# memory.net
KiCad netlist of a schematic drawn in EAGLE
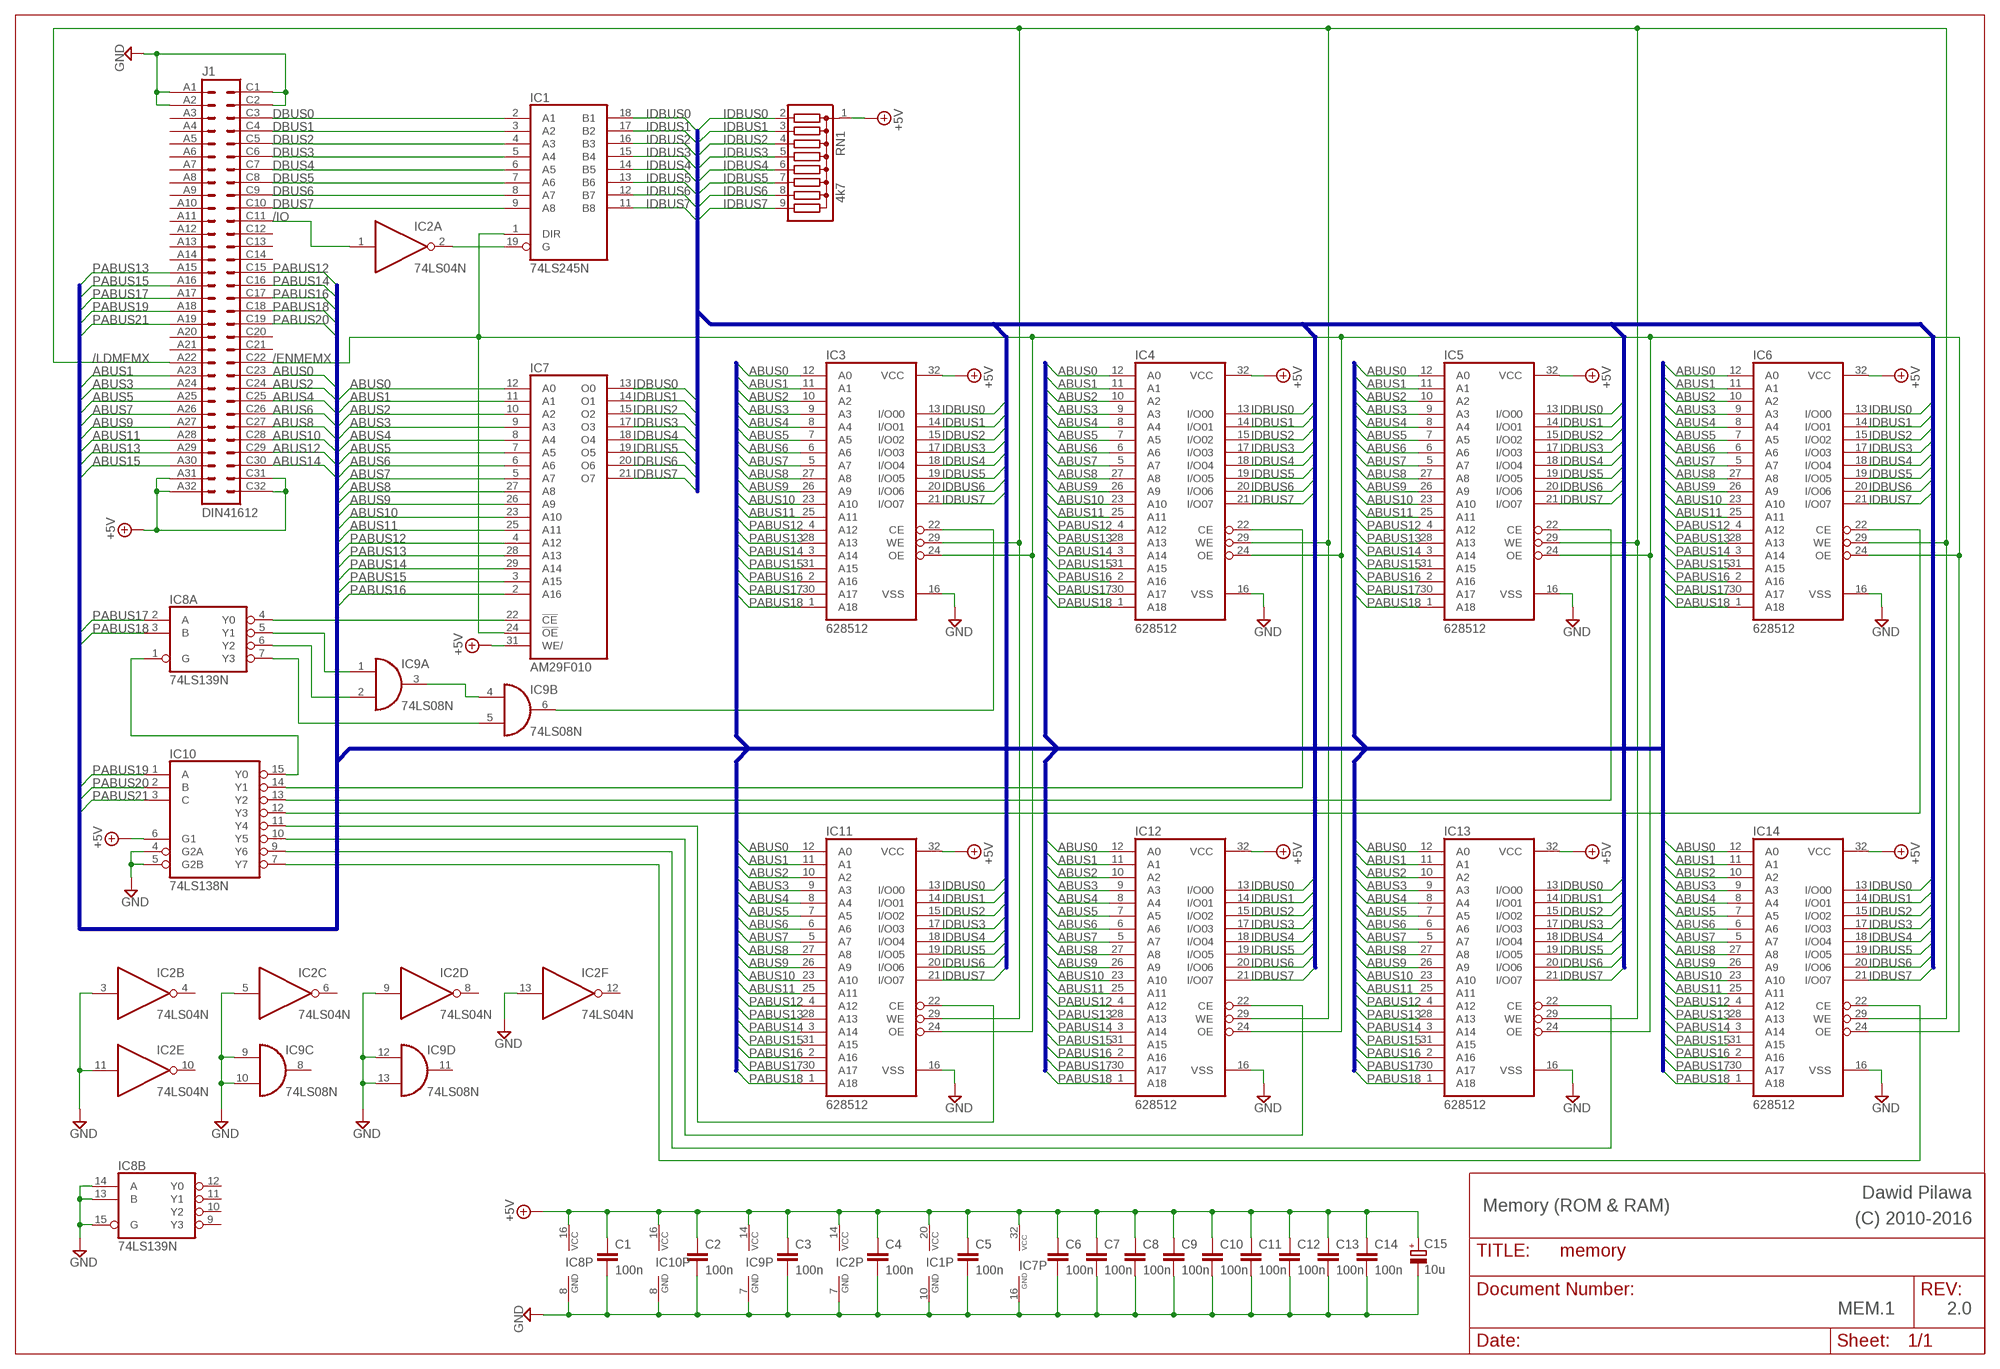
[diagram p0: schematic, sheet 1]

(export (version "E")
  (design (tool "Eeschema 10.0.6"))
  (components
    (comp (ref "C1")
      (value "100n")
      (footprint "eagle-import:C050-024X044")
      (libsource (lib "eagle-import") (part "C-EU050-024X044"))
    )
    (comp (ref "C2")
      (value "100n")
      (footprint "eagle-import:C050-024X044")
      (libsource (lib "eagle-import") (part "C-EU050-024X044"))
    )
    (comp (ref "C3")
      (value "100n")
      (footprint "eagle-import:C050-024X044")
      (libsource (lib "eagle-import") (part "C-EU050-024X044"))
    )
    (comp (ref "C4")
      (value "100n")
      (footprint "eagle-import:C050-024X044")
      (libsource (lib "eagle-import") (part "C-EU050-024X044"))
    )
    (comp (ref "C5")
      (value "100n")
      (footprint "eagle-import:C050-024X044")
      (libsource (lib "eagle-import") (part "C-EU050-024X044"))
    )
    (comp (ref "C6")
      (value "100n")
      (footprint "eagle-import:C050-024X044")
      (libsource (lib "eagle-import") (part "C-EU050-024X044"))
    )
    (comp (ref "C7")
      (value "100n")
      (footprint "eagle-import:C050-024X044")
      (libsource (lib "eagle-import") (part "C-EU050-024X044"))
    )
    (comp (ref "C8")
      (value "100n")
      (footprint "eagle-import:C050-024X044")
      (libsource (lib "eagle-import") (part "C-EU050-024X044"))
    )
    (comp (ref "C9")
      (value "100n")
      (footprint "eagle-import:C050-024X044")
      (libsource (lib "eagle-import") (part "C-EU050-024X044"))
    )
    (comp (ref "C10")
      (value "100n")
      (footprint "eagle-import:C050-024X044")
      (libsource (lib "eagle-import") (part "C-EU050-024X044"))
    )
    (comp (ref "C11")
      (value "100n")
      (footprint "eagle-import:C050-024X044")
      (libsource (lib "eagle-import") (part "C-EU050-024X044"))
    )
    (comp (ref "C12")
      (value "100n")
      (footprint "eagle-import:C050-024X044")
      (libsource (lib "eagle-import") (part "C-EU050-024X044"))
    )
    (comp (ref "C13")
      (value "100n")
      (footprint "eagle-import:C050-024X044")
      (libsource (lib "eagle-import") (part "C-EU050-024X044"))
    )
    (comp (ref "C14")
      (value "100n")
      (footprint "eagle-import:C050-024X044")
      (libsource (lib "eagle-import") (part "C-EU050-024X044"))
    )
    (comp (ref "C15")
      (value "10u")
      (footprint "eagle-import:E2,5-6")
      (libsource (lib "eagle-import") (part "CPOL-EUE2.5-6"))
    )
    (comp (ref "IC1")
      (value "74LS245N")
      (footprint "eagle-import:DIL20")
      (libsource (lib "eagle-import") (part "74245NLS"))
    )
    (comp (ref "IC2")
      (value "74LS04N")
      (footprint "eagle-import:DIL14")
      (libsource (lib "eagle-import") (part "7404NLS"))
    )
    (comp (ref "IC3")
      (value "628512")
      (footprint "eagle-import:DIL32")
      (libsource (lib "eagle-import") (part "HM628512A_DIL32"))
    )
    (comp (ref "IC4")
      (value "628512")
      (footprint "eagle-import:DIL32")
      (libsource (lib "eagle-import") (part "HM628512A_DIL32"))
    )
    (comp (ref "IC5")
      (value "628512")
      (footprint "eagle-import:DIL32")
      (libsource (lib "eagle-import") (part "HM628512A_DIL32"))
    )
    (comp (ref "IC6")
      (value "628512")
      (footprint "eagle-import:DIL32")
      (libsource (lib "eagle-import") (part "HM628512A_DIL32"))
    )
    (comp (ref "IC7")
      (value "AM29F010")
      (footprint "eagle-import:DIL32-6")
      (libsource (lib "eagle-import") (part "AM29F010"))
    )
    (comp (ref "IC8")
      (value "74LS139N")
      (footprint "eagle-import:DIL16")
      (libsource (lib "eagle-import") (part "74139NLS"))
    )
    (comp (ref "IC9")
      (value "74LS08N")
      (footprint "eagle-import:DIL14")
      (libsource (lib "eagle-import") (part "7408NLS"))
    )
    (comp (ref "IC10")
      (value "74LS138N")
      (footprint "eagle-import:DIL16")
      (libsource (lib "eagle-import") (part "74138NLS"))
    )
    (comp (ref "IC11")
      (value "628512")
      (footprint "eagle-import:DIL32")
      (libsource (lib "eagle-import") (part "HM628512A_DIL32"))
    )
    (comp (ref "IC12")
      (value "628512")
      (footprint "eagle-import:DIL32")
      (libsource (lib "eagle-import") (part "HM628512A_DIL32"))
    )
    (comp (ref "IC13")
      (value "628512")
      (footprint "eagle-import:DIL32")
      (libsource (lib "eagle-import") (part "HM628512A_DIL32"))
    )
    (comp (ref "IC14")
      (value "628512")
      (footprint "eagle-import:DIL32")
      (libsource (lib "eagle-import") (part "HM628512A_DIL32"))
    )
    (comp (ref "J1")
      (value "DIN41612")
      (footprint "eagle-import:VG64B")
      (libsource (lib "eagle-import") (part "VG64B"))
    )
    (comp (ref "RN1")
      (value "4k7")
      (footprint "eagle-import:SIL9")
      (libsource (lib "eagle-import") (part "G08R"))
    )
  )
  (nets
    (net (code "1") (name "+5V") (class "Default")
      (node (ref "C1") (pin "1") (pinfunction "1_1") (pintype "passive"))
      (node (ref "C10") (pin "1") (pinfunction "1_1") (pintype "passive"))
      (node (ref "C11") (pin "1") (pinfunction "1_1") (pintype "passive"))
      (node (ref "C12") (pin "1") (pinfunction "1_1") (pintype "passive"))
      (node (ref "C13") (pin "1") (pinfunction "1_1") (pintype "passive"))
      (node (ref "C14") (pin "1") (pinfunction "1_1") (pintype "passive"))
      (node (ref "C15") (pin "+") (pinfunction "+_+") (pintype "passive"))
      (node (ref "C2") (pin "1") (pinfunction "1_1") (pintype "passive"))
      (node (ref "C3") (pin "1") (pinfunction "1_1") (pintype "passive"))
      (node (ref "C4") (pin "1") (pinfunction "1_1") (pintype "passive"))
      (node (ref "C5") (pin "1") (pinfunction "1_1") (pintype "passive"))
      (node (ref "C6") (pin "1") (pinfunction "1_1") (pintype "passive"))
      (node (ref "C7") (pin "1") (pinfunction "1_1") (pintype "passive"))
      (node (ref "C8") (pin "1") (pinfunction "1_1") (pintype "passive"))
      (node (ref "C9") (pin "1") (pinfunction "1_1") (pintype "passive"))
      (node (ref "IC1") (pin "20") (pinfunction "VCC_20") (pintype "power_in"))
      (node (ref "IC10") (pin "16") (pinfunction "VCC_16") (pintype "power_in"))
      (node (ref "IC10") (pin "6") (pinfunction "G1_6") (pintype "input"))
      (node (ref "IC11") (pin "32") (pinfunction "VCC_32") (pintype "power_in"))
      (node (ref "IC12") (pin "32") (pinfunction "VCC_32") (pintype "power_in"))
      (node (ref "IC13") (pin "32") (pinfunction "VCC_32") (pintype "power_in"))
      (node (ref "IC14") (pin "32") (pinfunction "VCC_32") (pintype "power_in"))
      (node (ref "IC2") (pin "14") (pinfunction "VCC_14") (pintype "power_in"))
      (node (ref "IC3") (pin "32") (pinfunction "VCC_32") (pintype "power_in"))
      (node (ref "IC4") (pin "32") (pinfunction "VCC_32") (pintype "power_in"))
      (node (ref "IC5") (pin "32") (pinfunction "VCC_32") (pintype "power_in"))
      (node (ref "IC6") (pin "32") (pinfunction "VCC_32") (pintype "power_in"))
      (node (ref "IC7") (pin "31") (pinfunction "WE/_31") (pintype "input"))
      (node (ref "IC7") (pin "32") (pinfunction "VCC_32") (pintype "power_in"))
      (node (ref "IC8") (pin "16") (pinfunction "VCC_16") (pintype "power_in"))
      (node (ref "IC9") (pin "14") (pinfunction "VCC_14") (pintype "power_in"))
      (node (ref "J1") (pin "A31") (pinfunction "A31_A31") (pintype "passive"))
      (node (ref "J1") (pin "A32") (pinfunction "A32_A32") (pintype "passive"))
      (node (ref "J1") (pin "C31") (pinfunction "C31_C31") (pintype "passive"))
      (node (ref "J1") (pin "C32") (pinfunction "C32_C32") (pintype "passive"))
      (node (ref "RN1") (pin "1") (pinfunction "1_1") (pintype "passive"))
    )
    (net (code "2") (name "/ABUS0") (class "Default")
      (node (ref "IC11") (pin "12") (pinfunction "A0_12") (pintype "input"))
      (node (ref "IC12") (pin "12") (pinfunction "A0_12") (pintype "input"))
      (node (ref "IC13") (pin "12") (pinfunction "A0_12") (pintype "input"))
      (node (ref "IC14") (pin "12") (pinfunction "A0_12") (pintype "input"))
      (node (ref "IC3") (pin "12") (pinfunction "A0_12") (pintype "input"))
      (node (ref "IC4") (pin "12") (pinfunction "A0_12") (pintype "input"))
      (node (ref "IC5") (pin "12") (pinfunction "A0_12") (pintype "input"))
      (node (ref "IC6") (pin "12") (pinfunction "A0_12") (pintype "input"))
      (node (ref "IC7") (pin "12") (pinfunction "A0_12") (pintype "input"))
      (node (ref "J1") (pin "C23") (pinfunction "C23_C23") (pintype "passive"))
    )
    (net (code "3") (name "/ABUS1") (class "Default")
      (node (ref "IC11") (pin "11") (pinfunction "A1_11") (pintype "input"))
      (node (ref "IC12") (pin "11") (pinfunction "A1_11") (pintype "input"))
      (node (ref "IC13") (pin "11") (pinfunction "A1_11") (pintype "input"))
      (node (ref "IC14") (pin "11") (pinfunction "A1_11") (pintype "input"))
      (node (ref "IC3") (pin "11") (pinfunction "A1_11") (pintype "input"))
      (node (ref "IC4") (pin "11") (pinfunction "A1_11") (pintype "input"))
      (node (ref "IC5") (pin "11") (pinfunction "A1_11") (pintype "input"))
      (node (ref "IC6") (pin "11") (pinfunction "A1_11") (pintype "input"))
      (node (ref "IC7") (pin "11") (pinfunction "A1_11") (pintype "input"))
      (node (ref "J1") (pin "A23") (pinfunction "A23_A23") (pintype "passive"))
    )
    (net (code "4") (name "/ABUS2") (class "Default")
      (node (ref "IC11") (pin "10") (pinfunction "A2_10") (pintype "input"))
      (node (ref "IC12") (pin "10") (pinfunction "A2_10") (pintype "input"))
      (node (ref "IC13") (pin "10") (pinfunction "A2_10") (pintype "input"))
      (node (ref "IC14") (pin "10") (pinfunction "A2_10") (pintype "input"))
      (node (ref "IC3") (pin "10") (pinfunction "A2_10") (pintype "input"))
      (node (ref "IC4") (pin "10") (pinfunction "A2_10") (pintype "input"))
      (node (ref "IC5") (pin "10") (pinfunction "A2_10") (pintype "input"))
      (node (ref "IC6") (pin "10") (pinfunction "A2_10") (pintype "input"))
      (node (ref "IC7") (pin "10") (pinfunction "A2_10") (pintype "input"))
      (node (ref "J1") (pin "C24") (pinfunction "C24_C24") (pintype "passive"))
    )
    (net (code "5") (name "/ABUS3") (class "Default")
      (node (ref "IC11") (pin "9") (pinfunction "A3_9") (pintype "input"))
      (node (ref "IC12") (pin "9") (pinfunction "A3_9") (pintype "input"))
      (node (ref "IC13") (pin "9") (pinfunction "A3_9") (pintype "input"))
      (node (ref "IC14") (pin "9") (pinfunction "A3_9") (pintype "input"))
      (node (ref "IC3") (pin "9") (pinfunction "A3_9") (pintype "input"))
      (node (ref "IC4") (pin "9") (pinfunction "A3_9") (pintype "input"))
      (node (ref "IC5") (pin "9") (pinfunction "A3_9") (pintype "input"))
      (node (ref "IC6") (pin "9") (pinfunction "A3_9") (pintype "input"))
      (node (ref "IC7") (pin "9") (pinfunction "A3_9") (pintype "input"))
      (node (ref "J1") (pin "A24") (pinfunction "A24_A24") (pintype "passive"))
    )
    (net (code "6") (name "/ABUS4") (class "Default")
      (node (ref "IC11") (pin "8") (pinfunction "A4_8") (pintype "input"))
      (node (ref "IC12") (pin "8") (pinfunction "A4_8") (pintype "input"))
      (node (ref "IC13") (pin "8") (pinfunction "A4_8") (pintype "input"))
      (node (ref "IC14") (pin "8") (pinfunction "A4_8") (pintype "input"))
      (node (ref "IC3") (pin "8") (pinfunction "A4_8") (pintype "input"))
      (node (ref "IC4") (pin "8") (pinfunction "A4_8") (pintype "input"))
      (node (ref "IC5") (pin "8") (pinfunction "A4_8") (pintype "input"))
      (node (ref "IC6") (pin "8") (pinfunction "A4_8") (pintype "input"))
      (node (ref "IC7") (pin "8") (pinfunction "A4_8") (pintype "input"))
      (node (ref "J1") (pin "C25") (pinfunction "C25_C25") (pintype "passive"))
    )
    (net (code "7") (name "/ABUS5") (class "Default")
      (node (ref "IC11") (pin "7") (pinfunction "A5_7") (pintype "input"))
      (node (ref "IC12") (pin "7") (pinfunction "A5_7") (pintype "input"))
      (node (ref "IC13") (pin "7") (pinfunction "A5_7") (pintype "input"))
      (node (ref "IC14") (pin "7") (pinfunction "A5_7") (pintype "input"))
      (node (ref "IC3") (pin "7") (pinfunction "A5_7") (pintype "input"))
      (node (ref "IC4") (pin "7") (pinfunction "A5_7") (pintype "input"))
      (node (ref "IC5") (pin "7") (pinfunction "A5_7") (pintype "input"))
      (node (ref "IC6") (pin "7") (pinfunction "A5_7") (pintype "input"))
      (node (ref "IC7") (pin "7") (pinfunction "A5_7") (pintype "input"))
      (node (ref "J1") (pin "A25") (pinfunction "A25_A25") (pintype "passive"))
    )
    (net (code "8") (name "/ABUS6") (class "Default")
      (node (ref "IC11") (pin "6") (pinfunction "A6_6") (pintype "input"))
      (node (ref "IC12") (pin "6") (pinfunction "A6_6") (pintype "input"))
      (node (ref "IC13") (pin "6") (pinfunction "A6_6") (pintype "input"))
      (node (ref "IC14") (pin "6") (pinfunction "A6_6") (pintype "input"))
      (node (ref "IC3") (pin "6") (pinfunction "A6_6") (pintype "input"))
      (node (ref "IC4") (pin "6") (pinfunction "A6_6") (pintype "input"))
      (node (ref "IC5") (pin "6") (pinfunction "A6_6") (pintype "input"))
      (node (ref "IC6") (pin "6") (pinfunction "A6_6") (pintype "input"))
      (node (ref "IC7") (pin "6") (pinfunction "A6_6") (pintype "input"))
      (node (ref "J1") (pin "C26") (pinfunction "C26_C26") (pintype "passive"))
    )
    (net (code "9") (name "/ABUS7") (class "Default")
      (node (ref "IC11") (pin "5") (pinfunction "A7_5") (pintype "input"))
      (node (ref "IC12") (pin "5") (pinfunction "A7_5") (pintype "input"))
      (node (ref "IC13") (pin "5") (pinfunction "A7_5") (pintype "input"))
      (node (ref "IC14") (pin "5") (pinfunction "A7_5") (pintype "input"))
      (node (ref "IC3") (pin "5") (pinfunction "A7_5") (pintype "input"))
      (node (ref "IC4") (pin "5") (pinfunction "A7_5") (pintype "input"))
      (node (ref "IC5") (pin "5") (pinfunction "A7_5") (pintype "input"))
      (node (ref "IC6") (pin "5") (pinfunction "A7_5") (pintype "input"))
      (node (ref "IC7") (pin "5") (pinfunction "A7_5") (pintype "input"))
      (node (ref "J1") (pin "A26") (pinfunction "A26_A26") (pintype "passive"))
    )
    (net (code "10") (name "/ABUS8") (class "Default")
      (node (ref "IC11") (pin "27") (pinfunction "A8_27") (pintype "input"))
      (node (ref "IC12") (pin "27") (pinfunction "A8_27") (pintype "input"))
      (node (ref "IC13") (pin "27") (pinfunction "A8_27") (pintype "input"))
      (node (ref "IC14") (pin "27") (pinfunction "A8_27") (pintype "input"))
      (node (ref "IC3") (pin "27") (pinfunction "A8_27") (pintype "input"))
      (node (ref "IC4") (pin "27") (pinfunction "A8_27") (pintype "input"))
      (node (ref "IC5") (pin "27") (pinfunction "A8_27") (pintype "input"))
      (node (ref "IC6") (pin "27") (pinfunction "A8_27") (pintype "input"))
      (node (ref "IC7") (pin "27") (pinfunction "A8_27") (pintype "input"))
      (node (ref "J1") (pin "C27") (pinfunction "C27_C27") (pintype "passive"))
    )
    (net (code "11") (name "/ABUS9") (class "Default")
      (node (ref "IC11") (pin "26") (pinfunction "A9_26") (pintype "input"))
      (node (ref "IC12") (pin "26") (pinfunction "A9_26") (pintype "input"))
      (node (ref "IC13") (pin "26") (pinfunction "A9_26") (pintype "input"))
      (node (ref "IC14") (pin "26") (pinfunction "A9_26") (pintype "input"))
      (node (ref "IC3") (pin "26") (pinfunction "A9_26") (pintype "input"))
      (node (ref "IC4") (pin "26") (pinfunction "A9_26") (pintype "input"))
      (node (ref "IC5") (pin "26") (pinfunction "A9_26") (pintype "input"))
      (node (ref "IC6") (pin "26") (pinfunction "A9_26") (pintype "input"))
      (node (ref "IC7") (pin "26") (pinfunction "A9_26") (pintype "input"))
      (node (ref "J1") (pin "A27") (pinfunction "A27_A27") (pintype "passive"))
    )
    (net (code "12") (name "/ABUS10") (class "Default")
      (node (ref "IC11") (pin "23") (pinfunction "A10_23") (pintype "input"))
      (node (ref "IC12") (pin "23") (pinfunction "A10_23") (pintype "input"))
      (node (ref "IC13") (pin "23") (pinfunction "A10_23") (pintype "input"))
      (node (ref "IC14") (pin "23") (pinfunction "A10_23") (pintype "input"))
      (node (ref "IC3") (pin "23") (pinfunction "A10_23") (pintype "input"))
      (node (ref "IC4") (pin "23") (pinfunction "A10_23") (pintype "input"))
      (node (ref "IC5") (pin "23") (pinfunction "A10_23") (pintype "input"))
      (node (ref "IC6") (pin "23") (pinfunction "A10_23") (pintype "input"))
      (node (ref "IC7") (pin "23") (pinfunction "A10_23") (pintype "input"))
      (node (ref "J1") (pin "C28") (pinfunction "C28_C28") (pintype "passive"))
    )
    (net (code "13") (name "/ABUS11") (class "Default")
      (node (ref "IC11") (pin "25") (pinfunction "A11_25") (pintype "input"))
      (node (ref "IC12") (pin "25") (pinfunction "A11_25") (pintype "input"))
      (node (ref "IC13") (pin "25") (pinfunction "A11_25") (pintype "input"))
      (node (ref "IC14") (pin "25") (pinfunction "A11_25") (pintype "input"))
      (node (ref "IC3") (pin "25") (pinfunction "A11_25") (pintype "input"))
      (node (ref "IC4") (pin "25") (pinfunction "A11_25") (pintype "input"))
      (node (ref "IC5") (pin "25") (pinfunction "A11_25") (pintype "input"))
      (node (ref "IC6") (pin "25") (pinfunction "A11_25") (pintype "input"))
      (node (ref "IC7") (pin "25") (pinfunction "A11_25") (pintype "input"))
      (node (ref "J1") (pin "A28") (pinfunction "A28_A28") (pintype "passive"))
    )
    (net (code "14") (name "/ABUS12") (class "Default")
      (node (ref "J1") (pin "C29") (pinfunction "C29_C29") (pintype "passive"))
    )
    (net (code "15") (name "/ABUS13") (class "Default")
      (node (ref "J1") (pin "A29") (pinfunction "A29_A29") (pintype "passive"))
    )
    (net (code "16") (name "/ABUS14") (class "Default")
      (node (ref "J1") (pin "C30") (pinfunction "C30_C30") (pintype "passive"))
    )
    (net (code "17") (name "/ABUS15") (class "Default")
      (node (ref "J1") (pin "A30") (pinfunction "A30_A30") (pintype "passive"))
    )
    (net (code "18") (name "/DBUS0") (class "Default")
      (node (ref "IC1") (pin "2") (pinfunction "A1_2") (pintype "bidirectional"))
      (node (ref "J1") (pin "C3") (pinfunction "C3_C3") (pintype "passive"))
    )
    (net (code "19") (name "/DBUS1") (class "Default")
      (node (ref "IC1") (pin "3") (pinfunction "A2_3") (pintype "bidirectional"))
      (node (ref "J1") (pin "C4") (pinfunction "C4_C4") (pintype "passive"))
    )
    (net (code "20") (name "/DBUS2") (class "Default")
      (node (ref "IC1") (pin "4") (pinfunction "A3_4") (pintype "bidirectional"))
      (node (ref "J1") (pin "C5") (pinfunction "C5_C5") (pintype "passive"))
    )
    (net (code "21") (name "/DBUS3") (class "Default")
      (node (ref "IC1") (pin "5") (pinfunction "A4_5") (pintype "bidirectional"))
      (node (ref "J1") (pin "C6") (pinfunction "C6_C6") (pintype "passive"))
    )
    (net (code "22") (name "/DBUS4") (class "Default")
      (node (ref "IC1") (pin "6") (pinfunction "A5_6") (pintype "bidirectional"))
      (node (ref "J1") (pin "C7") (pinfunction "C7_C7") (pintype "passive"))
    )
    (net (code "23") (name "/DBUS5") (class "Default")
      (node (ref "IC1") (pin "7") (pinfunction "A6_7") (pintype "bidirectional"))
      (node (ref "J1") (pin "C8") (pinfunction "C8_C8") (pintype "passive"))
    )
    (net (code "24") (name "/DBUS6") (class "Default")
      (node (ref "IC1") (pin "8") (pinfunction "A7_8") (pintype "bidirectional"))
      (node (ref "J1") (pin "C9") (pinfunction "C9_C9") (pintype "passive"))
    )
    (net (code "25") (name "/DBUS7") (class "Default")
      (node (ref "IC1") (pin "9") (pinfunction "A8_9") (pintype "bidirectional"))
      (node (ref "J1") (pin "C10") (pinfunction "C10_C10") (pintype "passive"))
    )
    (net (code "26") (name "/IDBUS0") (class "Default")
      (node (ref "IC1") (pin "18") (pinfunction "B1_18") (pintype "bidirectional"))
      (node (ref "IC11") (pin "13") (pinfunction "I/O00_13") (pintype "bidirectional"))
      (node (ref "IC12") (pin "13") (pinfunction "I/O00_13") (pintype "bidirectional"))
      (node (ref "IC13") (pin "13") (pinfunction "I/O00_13") (pintype "bidirectional"))
      (node (ref "IC14") (pin "13") (pinfunction "I/O00_13") (pintype "bidirectional"))
      (node (ref "IC3") (pin "13") (pinfunction "I/O00_13") (pintype "bidirectional"))
      (node (ref "IC4") (pin "13") (pinfunction "I/O00_13") (pintype "bidirectional"))
      (node (ref "IC5") (pin "13") (pinfunction "I/O00_13") (pintype "bidirectional"))
      (node (ref "IC6") (pin "13") (pinfunction "I/O00_13") (pintype "bidirectional"))
      (node (ref "IC7") (pin "13") (pinfunction "O0_13") (pintype "tri_state"))
      (node (ref "RN1") (pin "2") (pinfunction "2_2") (pintype "passive"))
    )
    (net (code "27") (name "/IDBUS1") (class "Default")
      (node (ref "IC1") (pin "17") (pinfunction "B2_17") (pintype "bidirectional"))
      (node (ref "IC11") (pin "14") (pinfunction "I/O01_14") (pintype "bidirectional"))
      (node (ref "IC12") (pin "14") (pinfunction "I/O01_14") (pintype "bidirectional"))
      (node (ref "IC13") (pin "14") (pinfunction "I/O01_14") (pintype "bidirectional"))
      (node (ref "IC14") (pin "14") (pinfunction "I/O01_14") (pintype "bidirectional"))
      (node (ref "IC3") (pin "14") (pinfunction "I/O01_14") (pintype "bidirectional"))
      (node (ref "IC4") (pin "14") (pinfunction "I/O01_14") (pintype "bidirectional"))
      (node (ref "IC5") (pin "14") (pinfunction "I/O01_14") (pintype "bidirectional"))
      (node (ref "IC6") (pin "14") (pinfunction "I/O01_14") (pintype "bidirectional"))
      (node (ref "IC7") (pin "14") (pinfunction "O1_14") (pintype "tri_state"))
      (node (ref "RN1") (pin "3") (pinfunction "3_3") (pintype "passive"))
    )
    (net (code "28") (name "/IDBUS2") (class "Default")
      (node (ref "IC1") (pin "16") (pinfunction "B3_16") (pintype "bidirectional"))
      (node (ref "IC11") (pin "15") (pinfunction "I/O02_15") (pintype "bidirectional"))
      (node (ref "IC12") (pin "15") (pinfunction "I/O02_15") (pintype "bidirectional"))
      (node (ref "IC13") (pin "15") (pinfunction "I/O02_15") (pintype "bidirectional"))
      (node (ref "IC14") (pin "15") (pinfunction "I/O02_15") (pintype "bidirectional"))
      (node (ref "IC3") (pin "15") (pinfunction "I/O02_15") (pintype "bidirectional"))
      (node (ref "IC4") (pin "15") (pinfunction "I/O02_15") (pintype "bidirectional"))
      (node (ref "IC5") (pin "15") (pinfunction "I/O02_15") (pintype "bidirectional"))
      (node (ref "IC6") (pin "15") (pinfunction "I/O02_15") (pintype "bidirectional"))
      (node (ref "IC7") (pin "15") (pinfunction "O2_15") (pintype "tri_state"))
      (node (ref "RN1") (pin "4") (pinfunction "4_4") (pintype "passive"))
    )
    (net (code "29") (name "/IDBUS3") (class "Default")
      (node (ref "IC1") (pin "15") (pinfunction "B4_15") (pintype "bidirectional"))
      (node (ref "IC11") (pin "17") (pinfunction "I/O03_17") (pintype "bidirectional"))
      (node (ref "IC12") (pin "17") (pinfunction "I/O03_17") (pintype "bidirectional"))
      (node (ref "IC13") (pin "17") (pinfunction "I/O03_17") (pintype "bidirectional"))
      (node (ref "IC14") (pin "17") (pinfunction "I/O03_17") (pintype "bidirectional"))
      (node (ref "IC3") (pin "17") (pinfunction "I/O03_17") (pintype "bidirectional"))
      (node (ref "IC4") (pin "17") (pinfunction "I/O03_17") (pintype "bidirectional"))
      (node (ref "IC5") (pin "17") (pinfunction "I/O03_17") (pintype "bidirectional"))
      (node (ref "IC6") (pin "17") (pinfunction "I/O03_17") (pintype "bidirectional"))
      (node (ref "IC7") (pin "17") (pinfunction "O3_17") (pintype "tri_state"))
      (node (ref "RN1") (pin "5") (pinfunction "5_5") (pintype "passive"))
    )
    (net (code "30") (name "/IDBUS4") (class "Default")
      (node (ref "IC1") (pin "14") (pinfunction "B5_14") (pintype "bidirectional"))
      (node (ref "IC11") (pin "18") (pinfunction "I/O04_18") (pintype "bidirectional"))
      (node (ref "IC12") (pin "18") (pinfunction "I/O04_18") (pintype "bidirectional"))
      (node (ref "IC13") (pin "18") (pinfunction "I/O04_18") (pintype "bidirectional"))
      (node (ref "IC14") (pin "18") (pinfunction "I/O04_18") (pintype "bidirectional"))
      (node (ref "IC3") (pin "18") (pinfunction "I/O04_18") (pintype "bidirectional"))
      (node (ref "IC4") (pin "18") (pinfunction "I/O04_18") (pintype "bidirectional"))
      (node (ref "IC5") (pin "18") (pinfunction "I/O04_18") (pintype "bidirectional"))
      (node (ref "IC6") (pin "18") (pinfunction "I/O04_18") (pintype "bidirectional"))
      (node (ref "IC7") (pin "18") (pinfunction "O4_18") (pintype "tri_state"))
      (node (ref "RN1") (pin "6") (pinfunction "6_6") (pintype "passive"))
    )
    (net (code "31") (name "/IDBUS5") (class "Default")
      (node (ref "IC1") (pin "13") (pinfunction "B6_13") (pintype "bidirectional"))
      (node (ref "IC11") (pin "19") (pinfunction "I/O05_19") (pintype "bidirectional"))
      (node (ref "IC12") (pin "19") (pinfunction "I/O05_19") (pintype "bidirectional"))
      (node (ref "IC13") (pin "19") (pinfunction "I/O05_19") (pintype "bidirectional"))
      (node (ref "IC14") (pin "19") (pinfunction "I/O05_19") (pintype "bidirectional"))
      (node (ref "IC3") (pin "19") (pinfunction "I/O05_19") (pintype "bidirectional"))
      (node (ref "IC4") (pin "19") (pinfunction "I/O05_19") (pintype "bidirectional"))
      (node (ref "IC5") (pin "19") (pinfunction "I/O05_19") (pintype "bidirectional"))
      (node (ref "IC6") (pin "19") (pinfunction "I/O05_19") (pintype "bidirectional"))
      (node (ref "IC7") (pin "19") (pinfunction "O5_19") (pintype "tri_state"))
      (node (ref "RN1") (pin "7") (pinfunction "7_7") (pintype "passive"))
    )
    (net (code "32") (name "/IDBUS6") (class "Default")
      (node (ref "IC1") (pin "12") (pinfunction "B7_12") (pintype "bidirectional"))
      (node (ref "IC11") (pin "20") (pinfunction "I/O06_20") (pintype "bidirectional"))
      (node (ref "IC12") (pin "20") (pinfunction "I/O06_20") (pintype "bidirectional"))
      (node (ref "IC13") (pin "20") (pinfunction "I/O06_20") (pintype "bidirectional"))
      (node (ref "IC14") (pin "20") (pinfunction "I/O06_20") (pintype "bidirectional"))
      (node (ref "IC3") (pin "20") (pinfunction "I/O06_20") (pintype "bidirectional"))
      (node (ref "IC4") (pin "20") (pinfunction "I/O06_20") (pintype "bidirectional"))
      (node (ref "IC5") (pin "20") (pinfunction "I/O06_20") (pintype "bidirectional"))
      (node (ref "IC6") (pin "20") (pinfunction "I/O06_20") (pintype "bidirectional"))
      (node (ref "IC7") (pin "20") (pinfunction "O6_20") (pintype "tri_state"))
      (node (ref "RN1") (pin "8") (pinfunction "8_8") (pintype "passive"))
    )
    (net (code "33") (name "/IDBUS7") (class "Default")
      (node (ref "IC1") (pin "11") (pinfunction "B8_11") (pintype "bidirectional"))
      (node (ref "IC11") (pin "21") (pinfunction "I/O07_21") (pintype "bidirectional"))
      (node (ref "IC12") (pin "21") (pinfunction "I/O07_21") (pintype "bidirectional"))
      (node (ref "IC13") (pin "21") (pinfunction "I/O07_21") (pintype "bidirectional"))
      (node (ref "IC14") (pin "21") (pinfunction "I/O07_21") (pintype "bidirectional"))
      (node (ref "IC3") (pin "21") (pinfunction "I/O07_21") (pintype "bidirectional"))
      (node (ref "IC4") (pin "21") (pinfunction "I/O07_21") (pintype "bidirectional"))
      (node (ref "IC5") (pin "21") (pinfunction "I/O07_21") (pintype "bidirectional"))
      (node (ref "IC6") (pin "21") (pinfunction "I/O07_21") (pintype "bidirectional"))
      (node (ref "IC7") (pin "21") (pinfunction "O7_21") (pintype "tri_state"))
      (node (ref "RN1") (pin "9") (pinfunction "9_9") (pintype "passive"))
    )
    (net (code "34") (name "/PABUS12") (class "Default")
      (node (ref "IC11") (pin "4") (pinfunction "A12_4") (pintype "input"))
      (node (ref "IC12") (pin "4") (pinfunction "A12_4") (pintype "input"))
      (node (ref "IC13") (pin "4") (pinfunction "A12_4") (pintype "input"))
      (node (ref "IC14") (pin "4") (pinfunction "A12_4") (pintype "input"))
      (node (ref "IC3") (pin "4") (pinfunction "A12_4") (pintype "input"))
      (node (ref "IC4") (pin "4") (pinfunction "A12_4") (pintype "input"))
      (node (ref "IC5") (pin "4") (pinfunction "A12_4") (pintype "input"))
      (node (ref "IC6") (pin "4") (pinfunction "A12_4") (pintype "input"))
      (node (ref "IC7") (pin "4") (pinfunction "A12_4") (pintype "input"))
      (node (ref "J1") (pin "C15") (pinfunction "C15_C15") (pintype "passive"))
    )
    (net (code "35") (name "/PABUS13") (class "Default")
      (node (ref "IC11") (pin "28") (pinfunction "A13_28") (pintype "input"))
      (node (ref "IC12") (pin "28") (pinfunction "A13_28") (pintype "input"))
      (node (ref "IC13") (pin "28") (pinfunction "A13_28") (pintype "input"))
      (node (ref "IC14") (pin "28") (pinfunction "A13_28") (pintype "input"))
      (node (ref "IC3") (pin "28") (pinfunction "A13_28") (pintype "input"))
      (node (ref "IC4") (pin "28") (pinfunction "A13_28") (pintype "input"))
      (node (ref "IC5") (pin "28") (pinfunction "A13_28") (pintype "input"))
      (node (ref "IC6") (pin "28") (pinfunction "A13_28") (pintype "input"))
      (node (ref "IC7") (pin "28") (pinfunction "A13_28") (pintype "input"))
      (node (ref "J1") (pin "A15") (pinfunction "A15_A15") (pintype "passive"))
    )
    (net (code "36") (name "/PABUS14") (class "Default")
      (node (ref "IC11") (pin "3") (pinfunction "A14_3") (pintype "input"))
      (node (ref "IC12") (pin "3") (pinfunction "A14_3") (pintype "input"))
      (node (ref "IC13") (pin "3") (pinfunction "A14_3") (pintype "input"))
      (node (ref "IC14") (pin "3") (pinfunction "A14_3") (pintype "input"))
      (node (ref "IC3") (pin "3") (pinfunction "A14_3") (pintype "input"))
      (node (ref "IC4") (pin "3") (pinfunction "A14_3") (pintype "input"))
      (node (ref "IC5") (pin "3") (pinfunction "A14_3") (pintype "input"))
      (node (ref "IC6") (pin "3") (pinfunction "A14_3") (pintype "input"))
      (node (ref "IC7") (pin "29") (pinfunction "A14_29") (pintype "input"))
      (node (ref "J1") (pin "C16") (pinfunction "C16_C16") (pintype "passive"))
    )
    (net (code "37") (name "/PABUS15") (class "Default")
      (node (ref "IC11") (pin "31") (pinfunction "A15_31") (pintype "input"))
      (node (ref "IC12") (pin "31") (pinfunction "A15_31") (pintype "input"))
      (node (ref "IC13") (pin "31") (pinfunction "A15_31") (pintype "input"))
      (node (ref "IC14") (pin "31") (pinfunction "A15_31") (pintype "input"))
      (node (ref "IC3") (pin "31") (pinfunction "A15_31") (pintype "input"))
      (node (ref "IC4") (pin "31") (pinfunction "A15_31") (pintype "input"))
      (node (ref "IC5") (pin "31") (pinfunction "A15_31") (pintype "input"))
      (node (ref "IC6") (pin "31") (pinfunction "A15_31") (pintype "input"))
      (node (ref "IC7") (pin "3") (pinfunction "A15_3") (pintype "input"))
      (node (ref "J1") (pin "A16") (pinfunction "A16_A16") (pintype "passive"))
    )
    (net (code "38") (name "/PABUS16") (class "Default")
      (node (ref "IC11") (pin "2") (pinfunction "A16_2") (pintype "input"))
      (node (ref "IC12") (pin "2") (pinfunction "A16_2") (pintype "input"))
      (node (ref "IC13") (pin "2") (pinfunction "A16_2") (pintype "input"))
      (node (ref "IC14") (pin "2") (pinfunction "A16_2") (pintype "input"))
      (node (ref "IC3") (pin "2") (pinfunction "A16_2") (pintype "input"))
      (node (ref "IC4") (pin "2") (pinfunction "A16_2") (pintype "input"))
      (node (ref "IC5") (pin "2") (pinfunction "A16_2") (pintype "input"))
      (node (ref "IC6") (pin "2") (pinfunction "A16_2") (pintype "input"))
      (node (ref "IC7") (pin "2") (pinfunction "A16_2") (pintype "input"))
      (node (ref "J1") (pin "C17") (pinfunction "C17_C17") (pintype "passive"))
    )
    (net (code "39") (name "/PABUS17") (class "Default")
      (node (ref "IC11") (pin "30") (pinfunction "A17_30") (pintype "input"))
      (node (ref "IC12") (pin "30") (pinfunction "A17_30") (pintype "input"))
      (node (ref "IC13") (pin "30") (pinfunction "A17_30") (pintype "input"))
      (node (ref "IC14") (pin "30") (pinfunction "A17_30") (pintype "input"))
      (node (ref "IC3") (pin "30") (pinfunction "A17_30") (pintype "input"))
      (node (ref "IC4") (pin "30") (pinfunction "A17_30") (pintype "input"))
      (node (ref "IC5") (pin "30") (pinfunction "A17_30") (pintype "input"))
      (node (ref "IC6") (pin "30") (pinfunction "A17_30") (pintype "input"))
      (node (ref "IC8") (pin "2") (pinfunction "A_2") (pintype "input"))
      (node (ref "J1") (pin "A17") (pinfunction "A17_A17") (pintype "passive"))
    )
    (net (code "40") (name "/PABUS18") (class "Default")
      (node (ref "IC11") (pin "1") (pinfunction "A18_1") (pintype "input"))
      (node (ref "IC12") (pin "1") (pinfunction "A18_1") (pintype "input"))
      (node (ref "IC13") (pin "1") (pinfunction "A18_1") (pintype "input"))
      (node (ref "IC14") (pin "1") (pinfunction "A18_1") (pintype "input"))
      (node (ref "IC3") (pin "1") (pinfunction "A18_1") (pintype "input"))
      (node (ref "IC4") (pin "1") (pinfunction "A18_1") (pintype "input"))
      (node (ref "IC5") (pin "1") (pinfunction "A18_1") (pintype "input"))
      (node (ref "IC6") (pin "1") (pinfunction "A18_1") (pintype "input"))
      (node (ref "IC8") (pin "3") (pinfunction "B_3") (pintype "input"))
      (node (ref "J1") (pin "C18") (pinfunction "C18_C18") (pintype "passive"))
    )
    (net (code "41") (name "/PABUS19") (class "Default")
      (node (ref "IC10") (pin "1") (pinfunction "A_1") (pintype "input"))
      (node (ref "J1") (pin "A18") (pinfunction "A18_A18") (pintype "passive"))
    )
    (net (code "42") (name "/PABUS20") (class "Default")
      (node (ref "IC10") (pin "2") (pinfunction "B_2") (pintype "input"))
      (node (ref "J1") (pin "C19") (pinfunction "C19_C19") (pintype "passive"))
    )
    (net (code "43") (name "/PABUS21") (class "Default")
      (node (ref "IC10") (pin "3") (pinfunction "C_3") (pintype "input"))
      (node (ref "J1") (pin "A19") (pinfunction "A19_A19") (pintype "passive"))
    )
    (net (code "44") (name "/{slash}ENMEMX") (class "Default")
      (node (ref "IC1") (pin "1") (pinfunction "DIR_1") (pintype "input"))
      (node (ref "IC11") (pin "24") (pinfunction "OE_24") (pintype "input"))
      (node (ref "IC12") (pin "24") (pinfunction "OE_24") (pintype "input"))
      (node (ref "IC13") (pin "24") (pinfunction "OE_24") (pintype "input"))
      (node (ref "IC14") (pin "24") (pinfunction "OE_24") (pintype "input"))
      (node (ref "IC3") (pin "24") (pinfunction "OE_24") (pintype "input"))
      (node (ref "IC4") (pin "24") (pinfunction "OE_24") (pintype "input"))
      (node (ref "IC5") (pin "24") (pinfunction "OE_24") (pintype "input"))
      (node (ref "IC6") (pin "24") (pinfunction "OE_24") (pintype "input"))
      (node (ref "IC7") (pin "24") (pinfunction "~{OE}_24") (pintype "input"))
      (node (ref "J1") (pin "C22") (pinfunction "C22_C22") (pintype "passive"))
    )
    (net (code "45") (name "/{slash}IO") (class "Default")
      (node (ref "IC2") (pin "1") (pinfunction "I_1") (pintype "input"))
      (node (ref "J1") (pin "C11") (pinfunction "C11_C11") (pintype "passive"))
    )
    (net (code "46") (name "/{slash}LDMEMX") (class "Default")
      (node (ref "IC11") (pin "29") (pinfunction "WE_29") (pintype "input"))
      (node (ref "IC12") (pin "29") (pinfunction "WE_29") (pintype "input"))
      (node (ref "IC13") (pin "29") (pinfunction "WE_29") (pintype "input"))
      (node (ref "IC14") (pin "29") (pinfunction "WE_29") (pintype "input"))
      (node (ref "IC3") (pin "29") (pinfunction "WE_29") (pintype "input"))
      (node (ref "IC4") (pin "29") (pinfunction "WE_29") (pintype "input"))
      (node (ref "IC5") (pin "29") (pinfunction "WE_29") (pintype "input"))
      (node (ref "IC6") (pin "29") (pinfunction "WE_29") (pintype "input"))
      (node (ref "J1") (pin "A22") (pinfunction "A22_A22") (pintype "passive"))
    )
    (net (code "47") (name "GND") (class "Default")
      (node (ref "C1") (pin "2") (pinfunction "2_2") (pintype "passive"))
      (node (ref "C10") (pin "2") (pinfunction "2_2") (pintype "passive"))
      (node (ref "C11") (pin "2") (pinfunction "2_2") (pintype "passive"))
      (node (ref "C12") (pin "2") (pinfunction "2_2") (pintype "passive"))
      (node (ref "C13") (pin "2") (pinfunction "2_2") (pintype "passive"))
      (node (ref "C14") (pin "2") (pinfunction "2_2") (pintype "passive"))
      (node (ref "C15") (pin "-") (pinfunction "-_-") (pintype "passive"))
      (node (ref "C2") (pin "2") (pinfunction "2_2") (pintype "passive"))
      (node (ref "C3") (pin "2") (pinfunction "2_2") (pintype "passive"))
      (node (ref "C4") (pin "2") (pinfunction "2_2") (pintype "passive"))
      (node (ref "C5") (pin "2") (pinfunction "2_2") (pintype "passive"))
      (node (ref "C6") (pin "2") (pinfunction "2_2") (pintype "passive"))
      (node (ref "C7") (pin "2") (pinfunction "2_2") (pintype "passive"))
      (node (ref "C8") (pin "2") (pinfunction "2_2") (pintype "passive"))
      (node (ref "C9") (pin "2") (pinfunction "2_2") (pintype "passive"))
      (node (ref "IC1") (pin "10") (pinfunction "GND_10") (pintype "power_in"))
      (node (ref "IC10") (pin "4") (pinfunction "G2A_4") (pintype "input"))
      (node (ref "IC10") (pin "5") (pinfunction "G2B_5") (pintype "input"))
      (node (ref "IC10") (pin "8") (pinfunction "GND_8") (pintype "power_in"))
      (node (ref "IC11") (pin "16") (pinfunction "VSS_16") (pintype "power_in"))
      (node (ref "IC12") (pin "16") (pinfunction "VSS_16") (pintype "power_in"))
      (node (ref "IC13") (pin "16") (pinfunction "VSS_16") (pintype "power_in"))
      (node (ref "IC14") (pin "16") (pinfunction "VSS_16") (pintype "power_in"))
      (node (ref "IC2") (pin "11") (pinfunction "I_11") (pintype "input"))
      (node (ref "IC2") (pin "13") (pinfunction "I_13") (pintype "input"))
      (node (ref "IC2") (pin "3") (pinfunction "I_3") (pintype "input"))
      (node (ref "IC2") (pin "5") (pinfunction "I_5") (pintype "input"))
      (node (ref "IC2") (pin "7") (pinfunction "GND_7") (pintype "power_in"))
      (node (ref "IC2") (pin "9") (pinfunction "I_9") (pintype "input"))
      (node (ref "IC3") (pin "16") (pinfunction "VSS_16") (pintype "power_in"))
      (node (ref "IC4") (pin "16") (pinfunction "VSS_16") (pintype "power_in"))
      (node (ref "IC5") (pin "16") (pinfunction "VSS_16") (pintype "power_in"))
      (node (ref "IC6") (pin "16") (pinfunction "VSS_16") (pintype "power_in"))
      (node (ref "IC7") (pin "16") (pinfunction "GND_16") (pintype "power_in"))
      (node (ref "IC8") (pin "13") (pinfunction "B_13") (pintype "input"))
      (node (ref "IC8") (pin "14") (pinfunction "A_14") (pintype "input"))
      (node (ref "IC8") (pin "15") (pinfunction "G_15") (pintype "input"))
      (node (ref "IC8") (pin "8") (pinfunction "GND_8") (pintype "power_in"))
      (node (ref "IC9") (pin "10") (pinfunction "I1_10") (pintype "input"))
      (node (ref "IC9") (pin "12") (pinfunction "I0_12") (pintype "input"))
      (node (ref "IC9") (pin "13") (pinfunction "I1_13") (pintype "input"))
      (node (ref "IC9") (pin "7") (pinfunction "GND_7") (pintype "power_in"))
      (node (ref "IC9") (pin "9") (pinfunction "I0_9") (pintype "input"))
      (node (ref "J1") (pin "A1") (pinfunction "A1_A1") (pintype "passive"))
      (node (ref "J1") (pin "A2") (pinfunction "A2_A2") (pintype "passive"))
      (node (ref "J1") (pin "C1") (pinfunction "C1_C1") (pintype "passive"))
      (node (ref "J1") (pin "C2") (pinfunction "C2_C2") (pintype "passive"))
    )
    (net (code "48") (name "Net-(IC1A-G)") (class "Default")
      (node (ref "IC1") (pin "19") (pinfunction "G_19") (pintype "input"))
      (node (ref "IC2") (pin "2") (pinfunction "O_2") (pintype "output"))
    )
    (net (code "49") (name "Net-(IC3-CE)") (class "Default")
      (node (ref "IC3") (pin "22") (pinfunction "CE_22") (pintype "input"))
      (node (ref "IC9") (pin "6") (pinfunction "O_6") (pintype "output"))
    )
    (net (code "50") (name "Net-(IC7A-~{CE})") (class "Default")
      (node (ref "IC7") (pin "22") (pinfunction "~{CE}_22") (pintype "input"))
      (node (ref "IC8") (pin "4") (pinfunction "Y0_4") (pintype "output"))
    )
    (net (code "51") (name "Net-(IC8A-Y1)") (class "Default")
      (node (ref "IC8") (pin "5") (pinfunction "Y1_5") (pintype "output"))
      (node (ref "IC9") (pin "1") (pinfunction "I0_1") (pintype "input"))
    )
    (net (code "52") (name "Net-(IC8A-Y2)") (class "Default")
      (node (ref "IC8") (pin "6") (pinfunction "Y2_6") (pintype "output"))
      (node (ref "IC9") (pin "2") (pinfunction "I1_2") (pintype "input"))
    )
    (net (code "53") (name "Net-(IC8A-Y3)") (class "Default")
      (node (ref "IC8") (pin "7") (pinfunction "Y3_7") (pintype "output"))
      (node (ref "IC9") (pin "5") (pinfunction "I1_5") (pintype "input"))
    )
    (net (code "54") (name "Net-(IC9A-O)") (class "Default")
      (node (ref "IC9") (pin "3") (pinfunction "O_3") (pintype "output"))
      (node (ref "IC9") (pin "4") (pinfunction "I0_4") (pintype "input"))
    )
    (net (code "55") (name "Net-(IC10A-Y0)") (class "Default")
      (node (ref "IC10") (pin "15") (pinfunction "Y0_15") (pintype "output"))
      (node (ref "IC8") (pin "1") (pinfunction "G_1") (pintype "input"))
    )
    (net (code "56") (name "Net-(IC10A-Y1)") (class "Default")
      (node (ref "IC10") (pin "14") (pinfunction "Y1_14") (pintype "output"))
      (node (ref "IC4") (pin "22") (pinfunction "CE_22") (pintype "input"))
    )
    (net (code "57") (name "Net-(IC10A-Y2)") (class "Default")
      (node (ref "IC10") (pin "13") (pinfunction "Y2_13") (pintype "output"))
      (node (ref "IC5") (pin "22") (pinfunction "CE_22") (pintype "input"))
    )
    (net (code "58") (name "Net-(IC10A-Y3)") (class "Default")
      (node (ref "IC10") (pin "12") (pinfunction "Y3_12") (pintype "output"))
      (node (ref "IC6") (pin "22") (pinfunction "CE_22") (pintype "input"))
    )
    (net (code "59") (name "Net-(IC10A-Y4)") (class "Default")
      (node (ref "IC10") (pin "11") (pinfunction "Y4_11") (pintype "output"))
      (node (ref "IC11") (pin "22") (pinfunction "CE_22") (pintype "input"))
    )
    (net (code "60") (name "Net-(IC10A-Y5)") (class "Default")
      (node (ref "IC10") (pin "10") (pinfunction "Y5_10") (pintype "output"))
      (node (ref "IC12") (pin "22") (pinfunction "CE_22") (pintype "input"))
    )
    (net (code "61") (name "Net-(IC10A-Y6)") (class "Default")
      (node (ref "IC10") (pin "9") (pinfunction "Y6_9") (pintype "output"))
      (node (ref "IC13") (pin "22") (pinfunction "CE_22") (pintype "input"))
    )
    (net (code "62") (name "Net-(IC10A-Y7)") (class "Default")
      (node (ref "IC10") (pin "7") (pinfunction "Y7_7") (pintype "output"))
      (node (ref "IC14") (pin "22") (pinfunction "CE_22") (pintype "input"))
    )
    (net (code "63") (name "unconnected-(IC2B-O-Pad4)") (class "Default")
      (node (ref "IC2") (pin "4") (pinfunction "O_4") (pintype "output"))
    )
    (net (code "64") (name "unconnected-(IC2C-O-Pad6)") (class "Default")
      (node (ref "IC2") (pin "6") (pinfunction "O_6") (pintype "output"))
    )
    (net (code "65") (name "unconnected-(IC2D-O-Pad8)") (class "Default")
      (node (ref "IC2") (pin "8") (pinfunction "O_8") (pintype "output"))
    )
    (net (code "66") (name "unconnected-(IC2E-O-Pad10)") (class "Default")
      (node (ref "IC2") (pin "10") (pinfunction "O_10") (pintype "output"))
    )
    (net (code "67") (name "unconnected-(IC2F-O-Pad12)") (class "Default")
      (node (ref "IC2") (pin "12") (pinfunction "O_12") (pintype "output"))
    )
    (net (code "68") (name "unconnected-(IC8B-Y0-Pad12)") (class "Default")
      (node (ref "IC8") (pin "12") (pinfunction "Y0_12") (pintype "output"))
    )
    (net (code "69") (name "unconnected-(IC8B-Y1-Pad11)") (class "Default")
      (node (ref "IC8") (pin "11") (pinfunction "Y1_11") (pintype "output"))
    )
    (net (code "70") (name "unconnected-(IC8B-Y2-Pad10)") (class "Default")
      (node (ref "IC8") (pin "10") (pinfunction "Y2_10") (pintype "output"))
    )
    (net (code "71") (name "unconnected-(IC8B-Y3-Pad9)") (class "Default")
      (node (ref "IC8") (pin "9") (pinfunction "Y3_9") (pintype "output"))
    )
    (net (code "72") (name "unconnected-(IC9C-O-Pad8)") (class "Default")
      (node (ref "IC9") (pin "8") (pinfunction "O_8") (pintype "output"))
    )
    (net (code "73") (name "unconnected-(IC9D-O-Pad11)") (class "Default")
      (node (ref "IC9") (pin "11") (pinfunction "O_11") (pintype "output"))
    )
    (net (code "74") (name "unconnected-(J1-PadA3)") (class "Default")
      (node (ref "J1") (pin "A3") (pinfunction "A3_A3") (pintype "passive"))
    )
    (net (code "75") (name "unconnected-(J1-PadA4)") (class "Default")
      (node (ref "J1") (pin "A4") (pinfunction "A4_A4") (pintype "passive"))
    )
    (net (code "76") (name "unconnected-(J1-PadA5)") (class "Default")
      (node (ref "J1") (pin "A5") (pinfunction "A5_A5") (pintype "passive"))
    )
    (net (code "77") (name "unconnected-(J1-PadA6)") (class "Default")
      (node (ref "J1") (pin "A6") (pinfunction "A6_A6") (pintype "passive"))
    )
    (net (code "78") (name "unconnected-(J1-PadA7)") (class "Default")
      (node (ref "J1") (pin "A7") (pinfunction "A7_A7") (pintype "passive"))
    )
    (net (code "79") (name "unconnected-(J1-PadA8)") (class "Default")
      (node (ref "J1") (pin "A8") (pinfunction "A8_A8") (pintype "passive"))
    )
    (net (code "80") (name "unconnected-(J1-PadA9)") (class "Default")
      (node (ref "J1") (pin "A9") (pinfunction "A9_A9") (pintype "passive"))
    )
    (net (code "81") (name "unconnected-(J1-PadA10)") (class "Default")
      (node (ref "J1") (pin "A10") (pinfunction "A10_A10") (pintype "passive"))
    )
    (net (code "82") (name "unconnected-(J1-PadA11)") (class "Default")
      (node (ref "J1") (pin "A11") (pinfunction "A11_A11") (pintype "passive"))
    )
    (net (code "83") (name "unconnected-(J1-PadA12)") (class "Default")
      (node (ref "J1") (pin "A12") (pinfunction "A12_A12") (pintype "passive"))
    )
    (net (code "84") (name "unconnected-(J1-PadA13)") (class "Default")
      (node (ref "J1") (pin "A13") (pinfunction "A13_A13") (pintype "passive"))
    )
    (net (code "85") (name "unconnected-(J1-PadA14)") (class "Default")
      (node (ref "J1") (pin "A14") (pinfunction "A14_A14") (pintype "passive"))
    )
    (net (code "86") (name "unconnected-(J1-PadA20)") (class "Default")
      (node (ref "J1") (pin "A20") (pinfunction "A20_A20") (pintype "passive"))
    )
    (net (code "87") (name "unconnected-(J1-PadA21)") (class "Default")
      (node (ref "J1") (pin "A21") (pinfunction "A21_A21") (pintype "passive"))
    )
    (net (code "88") (name "unconnected-(J1-PadC12)") (class "Default")
      (node (ref "J1") (pin "C12") (pinfunction "C12_C12") (pintype "passive"))
    )
    (net (code "89") (name "unconnected-(J1-PadC13)") (class "Default")
      (node (ref "J1") (pin "C13") (pinfunction "C13_C13") (pintype "passive"))
    )
    (net (code "90") (name "unconnected-(J1-PadC14)") (class "Default")
      (node (ref "J1") (pin "C14") (pinfunction "C14_C14") (pintype "passive"))
    )
    (net (code "91") (name "unconnected-(J1-PadC20)") (class "Default")
      (node (ref "J1") (pin "C20") (pinfunction "C20_C20") (pintype "passive"))
    )
    (net (code "92") (name "unconnected-(J1-PadC21)") (class "Default")
      (node (ref "J1") (pin "C21") (pinfunction "C21_C21") (pintype "passive"))
    )
  )
)
